# phi-brain4ch-ctrl.net
KiCad netlist of a schematic drawn in EAGLE
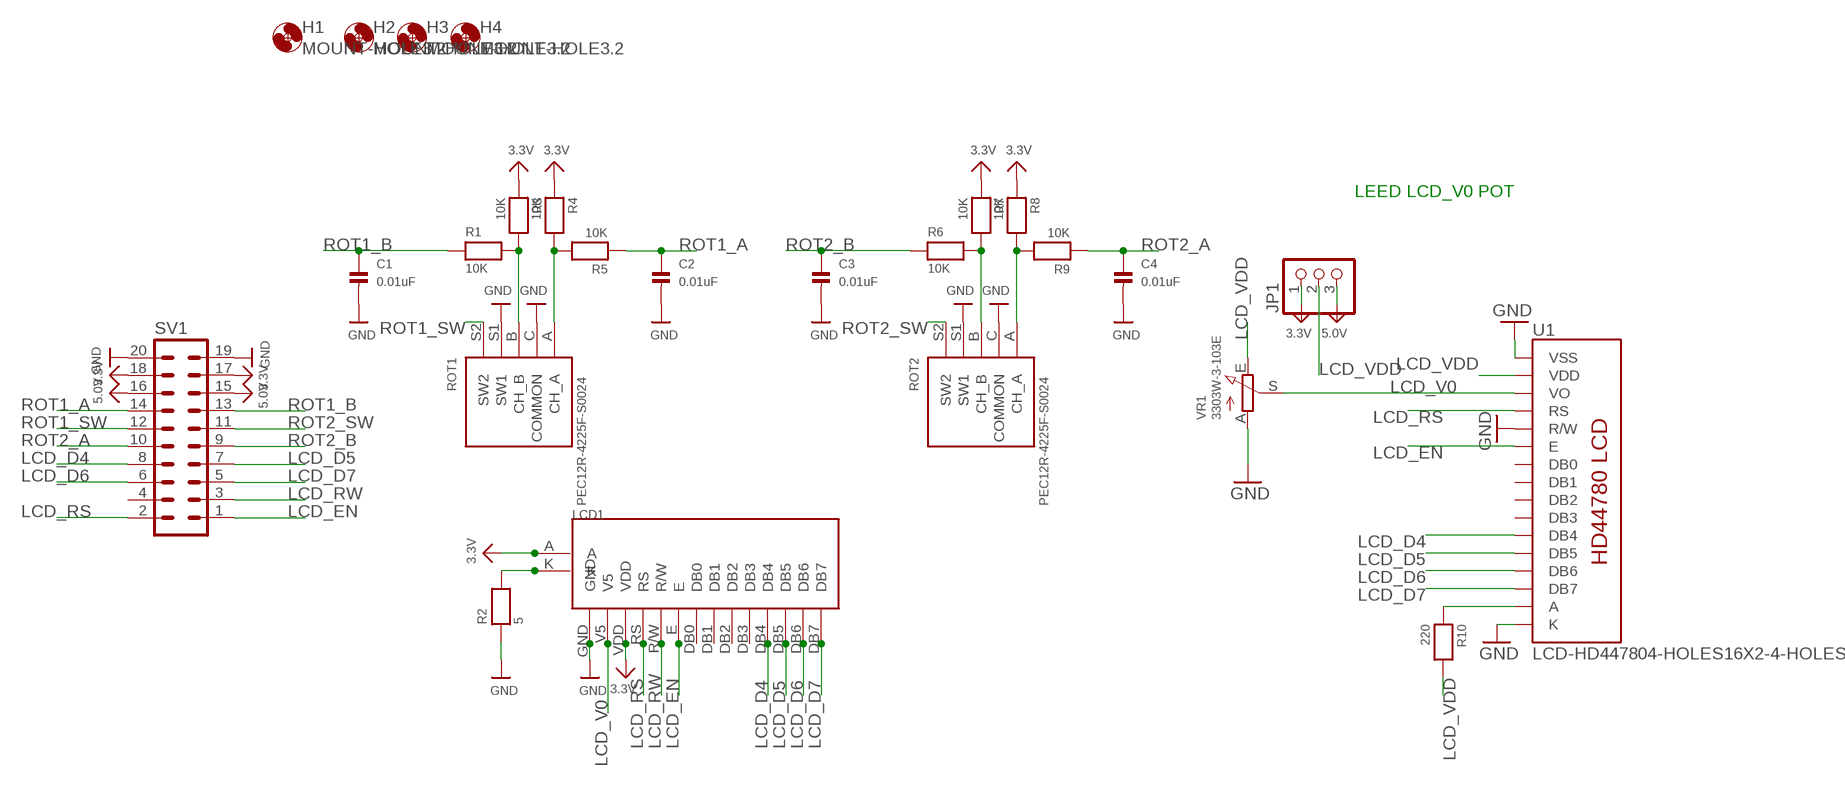
[diagram p0: schematic, sheet 1]

(export (version "E")
  (design (tool "Eeschema 10.0.6"))
  (components
    (comp (ref "C1")
      (value "0.01uF")
      (footprint "eagle-import:0805")
      (libsource (lib "eagle-import") (part "CAP_CERAMIC0805"))
    )
    (comp (ref "C2")
      (value "0.01uF")
      (footprint "eagle-import:0805")
      (libsource (lib "eagle-import") (part "CAP_CERAMIC0805"))
    )
    (comp (ref "C3")
      (value "0.01uF")
      (footprint "eagle-import:0805")
      (libsource (lib "eagle-import") (part "CAP_CERAMIC0805"))
    )
    (comp (ref "C4")
      (value "0.01uF")
      (footprint "eagle-import:0805")
      (libsource (lib "eagle-import") (part "CAP_CERAMIC0805"))
    )
    (comp (ref "H1")
      (value "MOUNT-HOLE3.2")
      (footprint "eagle-import:3,2")
      (libsource (lib "eagle-import") (part "MOUNT-HOLE3.2"))
    )
    (comp (ref "H2")
      (value "MOUNT-HOLE3.2")
      (footprint "eagle-import:3,2")
      (libsource (lib "eagle-import") (part "MOUNT-HOLE3.2"))
    )
    (comp (ref "H3")
      (value "MOUNT-HOLE3.2")
      (footprint "eagle-import:3,2")
      (libsource (lib "eagle-import") (part "MOUNT-HOLE3.2"))
    )
    (comp (ref "H4")
      (value "MOUNT-HOLE3.2")
      (footprint "eagle-import:3,2")
      (libsource (lib "eagle-import") (part "MOUNT-HOLE3.2"))
    )
    (comp (ref "JP1")
      (value "PINHD-1X3")
      (footprint "eagle-import:1X03")
      (libsource (lib "eagle-import") (part "PINHD-1X3"))
    )
    (comp (ref "LCD1")
      (value "NHD-C0220AA-FSW-FTW")
      (footprint "eagle-import:NHD-C0220AA-FSW-FTW")
      (libsource (lib "eagle-import") (part "NHD-C0220AA-FSW-FTW"))
    )
    (comp (ref "R1")
      (value "10K")
      (footprint "eagle-import:_0805")
      (libsource (lib "eagle-import") (part "RESISTOR_0805"))
    )
    (comp (ref "R2")
      (value "5")
      (footprint "eagle-import:_0805")
      (libsource (lib "eagle-import") (part "RESISTOR_0805"))
    )
    (comp (ref "R3")
      (value "10K")
      (footprint "eagle-import:_0805")
      (libsource (lib "eagle-import") (part "RESISTOR_0805"))
    )
    (comp (ref "R4")
      (value "10K")
      (footprint "eagle-import:_0805")
      (libsource (lib "eagle-import") (part "RESISTOR_0805"))
    )
    (comp (ref "R5")
      (value "10K")
      (footprint "eagle-import:_0805")
      (libsource (lib "eagle-import") (part "RESISTOR_0805"))
    )
    (comp (ref "R6")
      (value "10K")
      (footprint "eagle-import:_0805")
      (libsource (lib "eagle-import") (part "RESISTOR_0805"))
    )
    (comp (ref "R7")
      (value "10K")
      (footprint "eagle-import:_0805")
      (libsource (lib "eagle-import") (part "RESISTOR_0805"))
    )
    (comp (ref "R8")
      (value "10K")
      (footprint "eagle-import:_0805")
      (libsource (lib "eagle-import") (part "RESISTOR_0805"))
    )
    (comp (ref "R9")
      (value "10K")
      (footprint "eagle-import:_0805")
      (libsource (lib "eagle-import") (part "RESISTOR_0805"))
    )
    (comp (ref "R10")
      (value "220")
      (footprint "eagle-import:_0805")
      (libsource (lib "eagle-import") (part "RESISTOR_0805"))
    )
    (comp (ref "ROT1")
      (value "PEC12R-4225F-S0024")
      (footprint "eagle-import:PEC111-4XXXK-SXXXX")
      (libsource (lib "eagle-import") (part "PEC11-4215K-S0024"))
    )
    (comp (ref "ROT2")
      (value "PEC12R-4225F-S0024")
      (footprint "eagle-import:PEC111-4XXXK-SXXXX")
      (libsource (lib "eagle-import") (part "PEC11-4215K-S0024"))
    )
    (comp (ref "SV1")
      (value "ML203MSMT")
      (footprint "eagle-import:ML20SMT")
      (fields (field (name "PARTNO") "D2520-6V0C-AR-WE "))
      (libsource (lib "eagle-import") (part "ML203MSMT"))
    )
    (comp (ref "U1")
      (value "LCD-HD447804-HOLES16X2-4-HOLES")
      (footprint "eagle-import:LCD-16X2-4HOLES")
      (libsource (lib "eagle-import") (part "LCD-HD4478016X2-4-HOLES4-HOLES"))
    )
    (comp (ref "VR1")
      (value "3303W-3-103E")
      (footprint "eagle-import:TRIMPOT_BOURNS3MM")
      (libsource (lib "eagle-import") (part "TRIMPOT10K_BOURNS"))
    )
  )
  (nets
    (net (code "1") (name "/LCD_D4") (class "Default")
      (node (ref "LCD1") (pin "DB4") (pinfunction "DB4_DB4") (pintype "bidirectional"))
      (node (ref "SV1") (pin "8") (pinfunction "8_8") (pintype "passive"))
      (node (ref "U1") (pin "11") (pinfunction "DB4_11") (pintype "bidirectional"))
    )
    (net (code "2") (name "/LCD_D5") (class "Default")
      (node (ref "LCD1") (pin "DB5") (pinfunction "DB5_DB5") (pintype "bidirectional"))
      (node (ref "SV1") (pin "7") (pinfunction "7_7") (pintype "passive"))
      (node (ref "U1") (pin "12") (pinfunction "DB5_12") (pintype "bidirectional"))
    )
    (net (code "3") (name "/LCD_D6") (class "Default")
      (node (ref "LCD1") (pin "DB6") (pinfunction "DB6_DB6") (pintype "bidirectional"))
      (node (ref "SV1") (pin "6") (pinfunction "6_6") (pintype "passive"))
      (node (ref "U1") (pin "13") (pinfunction "DB6_13") (pintype "bidirectional"))
    )
    (net (code "4") (name "/LCD_D7") (class "Default")
      (node (ref "LCD1") (pin "DB7") (pinfunction "DB7_DB7") (pintype "bidirectional"))
      (node (ref "SV1") (pin "5") (pinfunction "5_5") (pintype "passive"))
      (node (ref "U1") (pin "14") (pinfunction "DB7_14") (pintype "bidirectional"))
    )
    (net (code "5") (name "/LCD_EN") (class "Default")
      (node (ref "LCD1") (pin "E") (pinfunction "E_E") (pintype "bidirectional"))
      (node (ref "SV1") (pin "1") (pinfunction "1_1") (pintype "passive"))
      (node (ref "U1") (pin "6") (pinfunction "E_6") (pintype "input"))
    )
    (net (code "6") (name "/LCD_RS") (class "Default")
      (node (ref "LCD1") (pin "RS") (pinfunction "RS_RS") (pintype "bidirectional"))
      (node (ref "SV1") (pin "2") (pinfunction "2_2") (pintype "passive"))
      (node (ref "U1") (pin "4") (pinfunction "RS_4") (pintype "input"))
    )
    (net (code "7") (name "/LCD_RW") (class "Default")
      (node (ref "LCD1") (pin "R/W") (pinfunction "R/W_R/W") (pintype "bidirectional"))
      (node (ref "SV1") (pin "3") (pinfunction "3_3") (pintype "passive"))
    )
    (net (code "8") (name "/LCD_V0") (class "Default")
      (node (ref "LCD1") (pin "V5") (pinfunction "V5_V5") (pintype "bidirectional"))
      (node (ref "U1") (pin "3") (pinfunction "VO_3") (pintype "bidirectional"))
      (node (ref "VR1") (pin "S") (pinfunction "S_S") (pintype "passive"))
    )
    (net (code "9") (name "/LCD_VDD") (class "Default")
      (node (ref "JP1") (pin "2") (pinfunction "2_2") (pintype "passive"))
      (node (ref "R10") (pin "2") (pinfunction "2_2") (pintype "passive"))
      (node (ref "U1") (pin "2") (pinfunction "VDD_2") (pintype "power_in"))
      (node (ref "VR1") (pin "E") (pinfunction "E_E") (pintype "passive"))
    )
    (net (code "10") (name "/ROT1_A") (class "Default")
      (node (ref "C2") (pin "1") (pinfunction "P$1_1") (pintype "passive"))
      (node (ref "R5") (pin "1") (pinfunction "1_1") (pintype "passive"))
      (node (ref "SV1") (pin "14") (pinfunction "14_14") (pintype "passive"))
    )
    (net (code "11") (name "/ROT1_B") (class "Default")
      (node (ref "C1") (pin "1") (pinfunction "P$1_1") (pintype "passive"))
      (node (ref "R1") (pin "1") (pinfunction "1_1") (pintype "passive"))
      (node (ref "SV1") (pin "13") (pinfunction "13_13") (pintype "passive"))
    )
    (net (code "12") (name "/ROT1_SW") (class "Default")
      (node (ref "ROT1") (pin "S2") (pinfunction "SW2_S2") (pintype "bidirectional"))
      (node (ref "SV1") (pin "12") (pinfunction "12_12") (pintype "passive"))
    )
    (net (code "13") (name "/ROT2_A") (class "Default")
      (node (ref "C4") (pin "1") (pinfunction "P$1_1") (pintype "passive"))
      (node (ref "R9") (pin "1") (pinfunction "1_1") (pintype "passive"))
      (node (ref "SV1") (pin "10") (pinfunction "10_10") (pintype "passive"))
    )
    (net (code "14") (name "/ROT2_B") (class "Default")
      (node (ref "C3") (pin "1") (pinfunction "P$1_1") (pintype "passive"))
      (node (ref "R6") (pin "1") (pinfunction "1_1") (pintype "passive"))
      (node (ref "SV1") (pin "9") (pinfunction "9_9") (pintype "passive"))
    )
    (net (code "15") (name "/ROT2_SW") (class "Default")
      (node (ref "ROT2") (pin "S2") (pinfunction "SW2_S2") (pintype "bidirectional"))
      (node (ref "SV1") (pin "11") (pinfunction "11_11") (pintype "passive"))
    )
    (net (code "16") (name "3.3V") (class "Default")
      (node (ref "JP1") (pin "1") (pinfunction "1_1") (pintype "passive"))
      (node (ref "LCD1") (pin "A") (pinfunction "A_A") (pintype "bidirectional"))
      (node (ref "LCD1") (pin "VDD") (pinfunction "VDD_VDD") (pintype "bidirectional"))
      (node (ref "R3") (pin "1") (pinfunction "1_1") (pintype "passive"))
      (node (ref "R4") (pin "1") (pinfunction "1_1") (pintype "passive"))
      (node (ref "R7") (pin "1") (pinfunction "1_1") (pintype "passive"))
      (node (ref "R8") (pin "1") (pinfunction "1_1") (pintype "passive"))
      (node (ref "SV1") (pin "17") (pinfunction "17_17") (pintype "passive"))
      (node (ref "SV1") (pin "18") (pinfunction "18_18") (pintype "passive"))
    )
    (net (code "17") (name "5.0V") (class "Default")
      (node (ref "JP1") (pin "3") (pinfunction "3_3") (pintype "passive"))
      (node (ref "SV1") (pin "15") (pinfunction "15_15") (pintype "passive"))
      (node (ref "SV1") (pin "16") (pinfunction "16_16") (pintype "passive"))
    )
    (net (code "18") (name "GND") (class "Default")
      (node (ref "C1") (pin "2") (pinfunction "P$2_2") (pintype "passive"))
      (node (ref "C2") (pin "2") (pinfunction "P$2_2") (pintype "passive"))
      (node (ref "C3") (pin "2") (pinfunction "P$2_2") (pintype "passive"))
      (node (ref "C4") (pin "2") (pinfunction "P$2_2") (pintype "passive"))
      (node (ref "LCD1") (pin "GND") (pinfunction "GND_GND") (pintype "bidirectional"))
      (node (ref "R2") (pin "1") (pinfunction "1_1") (pintype "passive"))
      (node (ref "ROT1") (pin "C") (pinfunction "COMMON_C") (pintype "input"))
      (node (ref "ROT1") (pin "S1") (pinfunction "SW1_S1") (pintype "bidirectional"))
      (node (ref "ROT2") (pin "C") (pinfunction "COMMON_C") (pintype "input"))
      (node (ref "ROT2") (pin "S1") (pinfunction "SW1_S1") (pintype "bidirectional"))
      (node (ref "SV1") (pin "19") (pinfunction "19_19") (pintype "passive"))
      (node (ref "SV1") (pin "20") (pinfunction "20_20") (pintype "passive"))
      (node (ref "U1") (pin "1") (pinfunction "VSS_1") (pintype "power_in"))
      (node (ref "U1") (pin "16") (pinfunction "K_16") (pintype "power_in"))
      (node (ref "U1") (pin "5") (pinfunction "R/W_5") (pintype "input"))
      (node (ref "VR1") (pin "A") (pinfunction "A_A") (pintype "passive"))
    )
    (net (code "19") (name "Net-(LCD1-PadK)") (class "Default")
      (node (ref "LCD1") (pin "K") (pinfunction "K_K") (pintype "bidirectional"))
      (node (ref "R2") (pin "2") (pinfunction "2_2") (pintype "passive"))
    )
    (net (code "20") (name "Net-(ROT1-CH_A)") (class "Default")
      (node (ref "R4") (pin "2") (pinfunction "2_2") (pintype "passive"))
      (node (ref "R5") (pin "2") (pinfunction "2_2") (pintype "passive"))
      (node (ref "ROT1") (pin "A") (pinfunction "CH_A_A") (pintype "output"))
    )
    (net (code "21") (name "Net-(ROT1-CH_B)") (class "Default")
      (node (ref "R1") (pin "2") (pinfunction "2_2") (pintype "passive"))
      (node (ref "R3") (pin "2") (pinfunction "2_2") (pintype "passive"))
      (node (ref "ROT1") (pin "B") (pinfunction "CH_B_B") (pintype "output"))
    )
    (net (code "22") (name "Net-(ROT2-CH_A)") (class "Default")
      (node (ref "R8") (pin "2") (pinfunction "2_2") (pintype "passive"))
      (node (ref "R9") (pin "2") (pinfunction "2_2") (pintype "passive"))
      (node (ref "ROT2") (pin "A") (pinfunction "CH_A_A") (pintype "output"))
    )
    (net (code "23") (name "Net-(ROT2-CH_B)") (class "Default")
      (node (ref "R6") (pin "2") (pinfunction "2_2") (pintype "passive"))
      (node (ref "R7") (pin "2") (pinfunction "2_2") (pintype "passive"))
      (node (ref "ROT2") (pin "B") (pinfunction "CH_B_B") (pintype "output"))
    )
    (net (code "24") (name "Net-(U1-A)") (class "Default")
      (node (ref "R10") (pin "1") (pinfunction "1_1") (pintype "passive"))
      (node (ref "U1") (pin "15") (pinfunction "A_15") (pintype "power_in"))
    )
    (net (code "25") (name "unconnected-(LCD1-PadDB0)") (class "Default")
      (node (ref "LCD1") (pin "DB0") (pinfunction "DB0_DB0") (pintype "bidirectional"))
    )
    (net (code "26") (name "unconnected-(LCD1-PadDB1)") (class "Default")
      (node (ref "LCD1") (pin "DB1") (pinfunction "DB1_DB1") (pintype "bidirectional"))
    )
    (net (code "27") (name "unconnected-(LCD1-PadDB2)") (class "Default")
      (node (ref "LCD1") (pin "DB2") (pinfunction "DB2_DB2") (pintype "bidirectional"))
    )
    (net (code "28") (name "unconnected-(LCD1-PadDB3)") (class "Default")
      (node (ref "LCD1") (pin "DB3") (pinfunction "DB3_DB3") (pintype "bidirectional"))
    )
    (net (code "29") (name "unconnected-(SV1-Pad4)") (class "Default")
      (node (ref "SV1") (pin "4") (pinfunction "4_4") (pintype "passive"))
    )
    (net (code "30") (name "unconnected-(U1-DB0-Pad7)") (class "Default")
      (node (ref "U1") (pin "7") (pinfunction "DB0_7") (pintype "bidirectional"))
    )
    (net (code "31") (name "unconnected-(U1-DB1-Pad8)") (class "Default")
      (node (ref "U1") (pin "8") (pinfunction "DB1_8") (pintype "bidirectional"))
    )
    (net (code "32") (name "unconnected-(U1-DB2-Pad9)") (class "Default")
      (node (ref "U1") (pin "9") (pinfunction "DB2_9") (pintype "bidirectional"))
    )
    (net (code "33") (name "unconnected-(U1-DB3-Pad10)") (class "Default")
      (node (ref "U1") (pin "10") (pinfunction "DB3_10") (pintype "bidirectional"))
    )
  )
)
